# WiFiSensorLTC3559Spansion.net
KiCad netlist of a schematic drawn in EAGLE
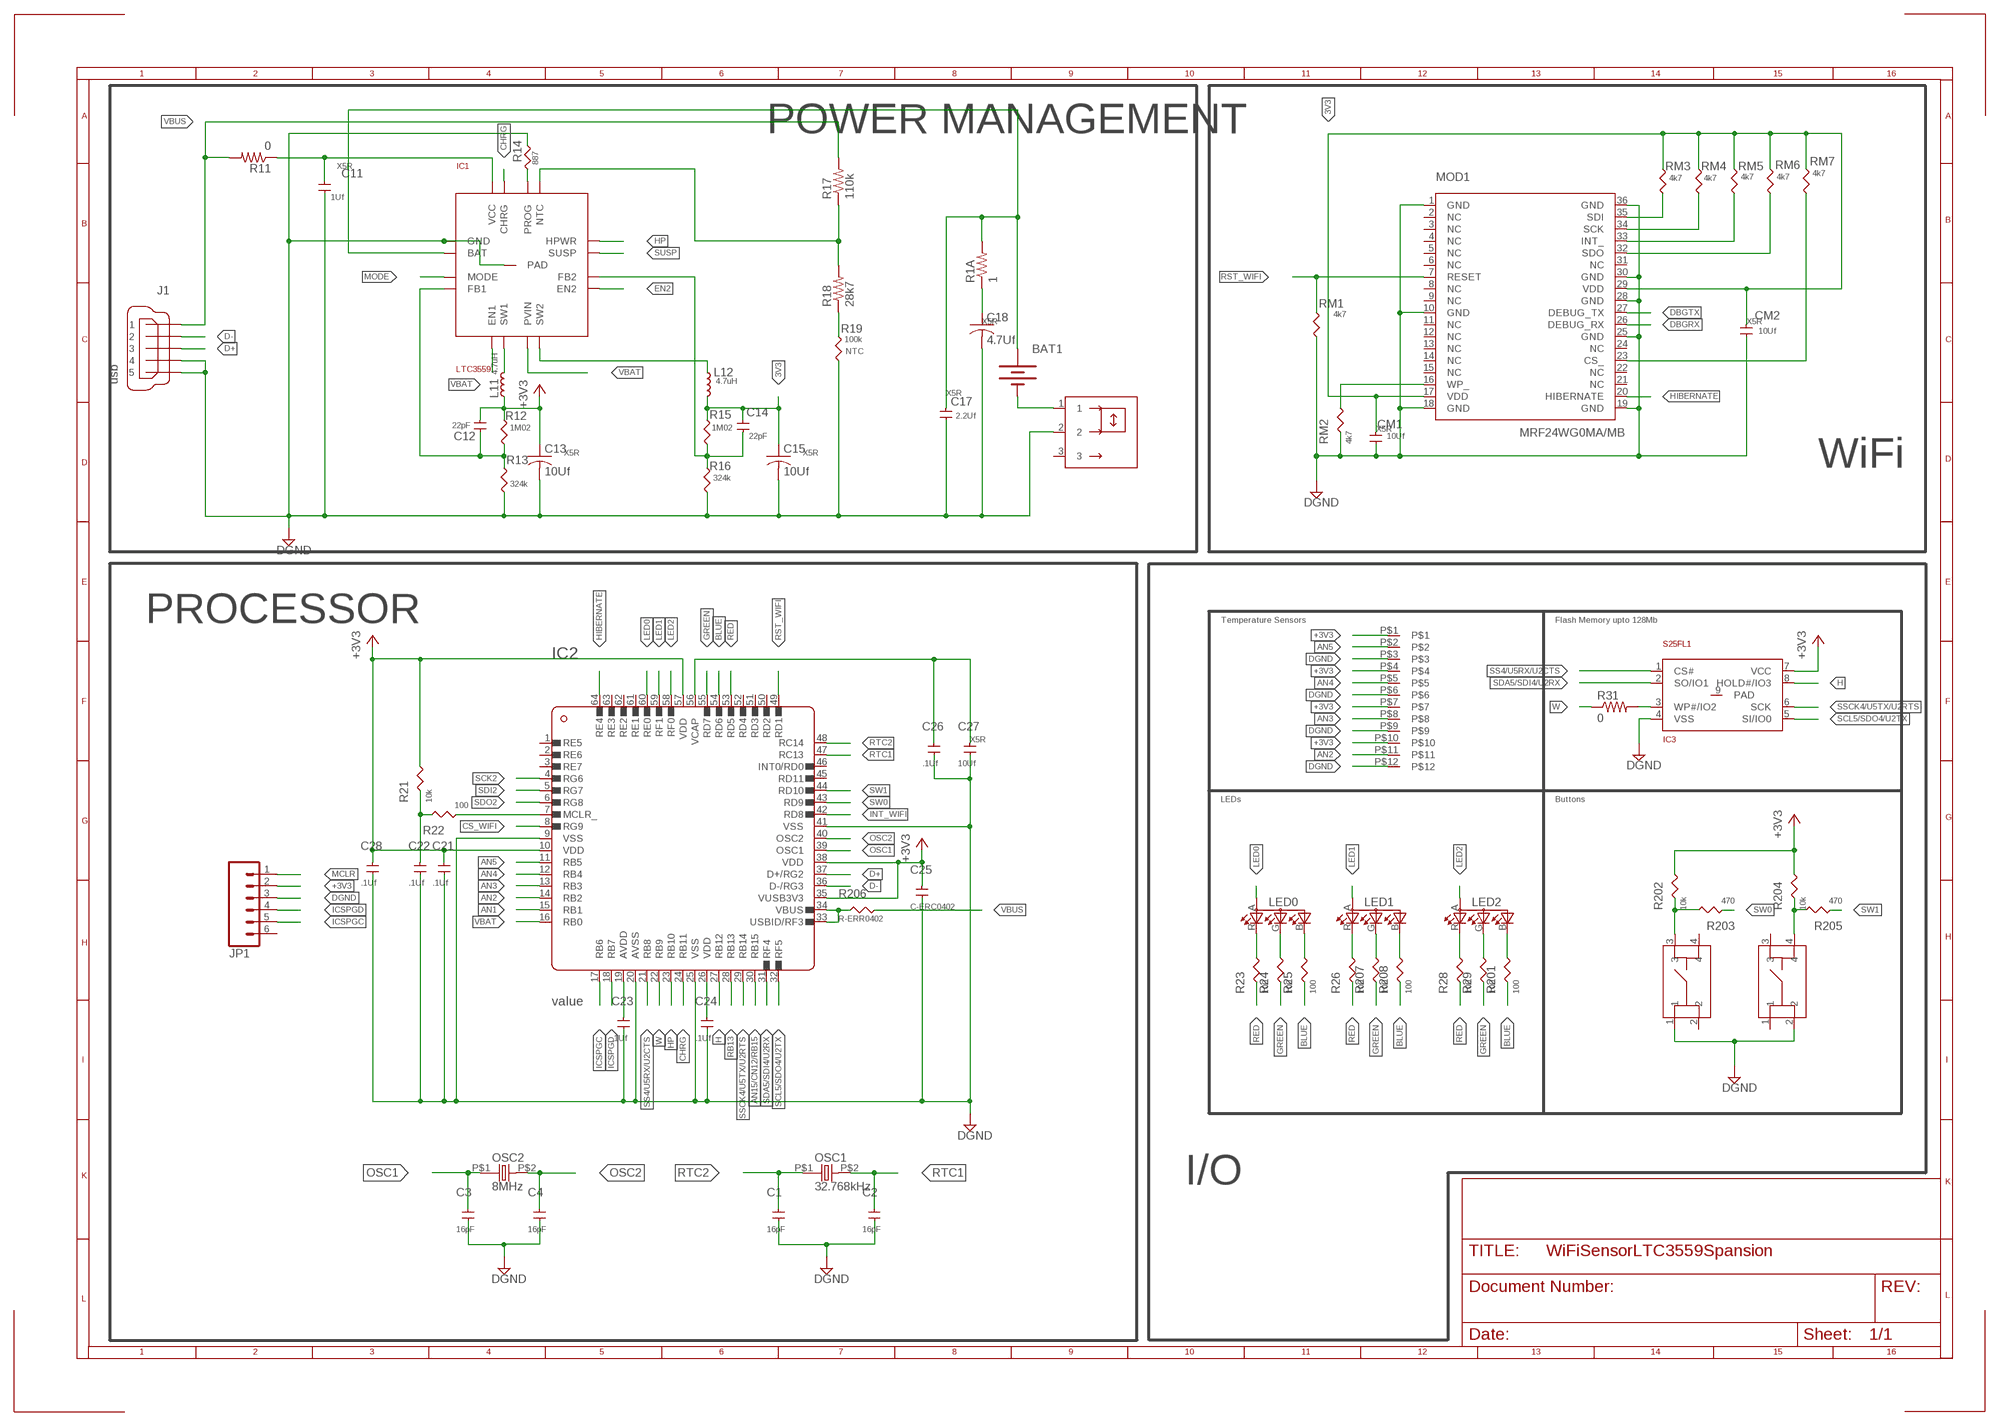
[diagram p0: schematic, sheet 1]

(export (version "E")
  (design (tool "Eeschema 10.0.6"))
  (components
    (comp (ref "BAT1")
      (value "BATTERY245PTH")
      (footprint "eagle-import:BATTCON_245MM_PTH")
      (libsource (lib "eagle-import") (part "BATTERY245PTH"))
    )
    (comp (ref "C1")
      (value "16pF")
      (footprint "eagle-import:C0402")
      (libsource (lib "eagle-import") (part "C-ERC0402"))
    )
    (comp (ref "C2")
      (value "16pF")
      (footprint "eagle-import:C0402")
      (libsource (lib "eagle-import") (part "C-ERC0402"))
    )
    (comp (ref "C3")
      (value "16pF")
      (footprint "eagle-import:C0402")
      (libsource (lib "eagle-import") (part "C-ERC0402"))
    )
    (comp (ref "C4")
      (value "16pF")
      (footprint "eagle-import:C0402")
      (libsource (lib "eagle-import") (part "C-ERC0402"))
    )
    (comp (ref "C11")
      (value "1Uf")
      (footprint "eagle-import:C0805")
      (fields (field (name "TEMPCHAR") "X5R"))
      (libsource (lib "eagle-import") (part "C-ER"))
    )
    (comp (ref "C12")
      (value "22pF")
      (footprint "eagle-import:C0402")
      (libsource (lib "eagle-import") (part "C-ERC0402"))
    )
    (comp (ref "C13")
      (value "10Uf")
      (footprint "eagle-import:C0805")
      (fields (field (name "TEMPCHAR") "X5R"))
      (libsource (lib "eagle-import") (part "C-USC0805"))
    )
    (comp (ref "C14")
      (value "22pF")
      (footprint "eagle-import:C0402")
      (libsource (lib "eagle-import") (part "C-ERC0402"))
    )
    (comp (ref "C15")
      (value "10Uf")
      (footprint "eagle-import:C0805")
      (fields (field (name "TEMPCHAR") "X5R"))
      (libsource (lib "eagle-import") (part "C-USC0805"))
    )
    (comp (ref "C17")
      (value "2.2Uf")
      (footprint "eagle-import:C0805")
      (fields (field (name "TEMPCHAR") "X5R"))
      (libsource (lib "eagle-import") (part "C-ER"))
    )
    (comp (ref "C18")
      (value "4.7Uf")
      (footprint "eagle-import:C0402")
      (fields (field (name "TEMPCHAR") "X5R"))
      (libsource (lib "eagle-import") (part "C-USC0402"))
    )
    (comp (ref "C21")
      (value ".1Uf")
      (footprint "eagle-import:C0402")
      (libsource (lib "eagle-import") (part "C-ERC0402"))
    )
    (comp (ref "C22")
      (value ".1Uf")
      (footprint "eagle-import:C0402")
      (libsource (lib "eagle-import") (part "C-ERC0402"))
    )
    (comp (ref "C23")
      (value ".1Uf")
      (footprint "eagle-import:C0402")
      (libsource (lib "eagle-import") (part "C-ERC0402"))
    )
    (comp (ref "C24")
      (value ".1Uf")
      (footprint "eagle-import:C0402")
      (libsource (lib "eagle-import") (part "C-ERC0402"))
    )
    (comp (ref "C25")
      (value "C-ERC0402")
      (footprint "eagle-import:C0402")
      (libsource (lib "eagle-import") (part "C-ERC0402"))
    )
    (comp (ref "C26")
      (value ".1Uf")
      (footprint "eagle-import:C0402")
      (libsource (lib "eagle-import") (part "C-ERC0402"))
    )
    (comp (ref "C27")
      (value "10Uf")
      (footprint "eagle-import:C0805")
      (fields (field (name "TEMPCHAR") "X5R"))
      (libsource (lib "eagle-import") (part "C-ER"))
    )
    (comp (ref "C28")
      (value ".1Uf")
      (footprint "eagle-import:C0402")
      (libsource (lib "eagle-import") (part "C-ERC0402"))
    )
    (comp (ref "CM1")
      (value "10Uf")
      (footprint "eagle-import:C0805")
      (fields (field (name "TEMPCHAR") "X5R"))
      (libsource (lib "eagle-import") (part "C-ER"))
    )
    (comp (ref "CM2")
      (value "10Uf")
      (footprint "eagle-import:C0805")
      (fields (field (name "TEMPCHAR") "X5R"))
      (libsource (lib "eagle-import") (part "C-ER"))
    )
    (comp (ref "IC1")
      (value "LTC3559")
      (footprint "eagle-import:QFN16")
      (libsource (lib "eagle-import") (part "LTC3559"))
    )
    (comp (ref "IC2")
      (value "PICMX32695F512H")
      (footprint "eagle-import:TQFP64")
      (libsource (lib "eagle-import") (part "PICMX32695F512H"))
    )
    (comp (ref "IC3")
      (value "S25FL1")
      (footprint "eagle-import:8WSON")
      (libsource (lib "eagle-import") (part "S25FL1"))
    )
    (comp (ref "J1")
      (value "usb")
      (footprint "eagle-import:UX60A-MB-5ST")
      (libsource (lib "eagle-import") (part "MINI-USB-UX60A-MB-5ST"))
    )
    (comp (ref "JP1")
      (value "M06LOCK")
      (footprint "eagle-import:1X06_LOCK")
      (libsource (lib "eagle-import") (part "M06LOCK"))
    )
    (comp (ref "L11")
      (value "4.7uH")
      (footprint "eagle-import:L3010")
      (libsource (lib "eagle-import") (part "L-ER"))
    )
    (comp (ref "L12")
      (value "4.7uH")
      (footprint "eagle-import:L3010")
      (libsource (lib "eagle-import") (part "L-ER"))
    )
    (comp (ref "LED0")
      (value "1X1RGB")
      (footprint "eagle-import:1X1")
      (libsource (lib "eagle-import") (part "1X1RGB"))
    )
    (comp (ref "LED1")
      (value "1X1RGB")
      (footprint "eagle-import:1X1")
      (libsource (lib "eagle-import") (part "1X1RGB"))
    )
    (comp (ref "LED2")
      (value "1X1RGB")
      (footprint "eagle-import:1X1")
      (libsource (lib "eagle-import") (part "1X1RGB"))
    )
    (comp (ref "MOD1")
      (value "MRF24WG0MA/MB")
      (footprint "eagle-import:MRF24")
      (libsource (lib "eagle-import") (part "MRF24WG0MA/MB"))
    )
    (comp (ref "OSC1")
      (value "32.768kHz")
      (footprint "eagle-import:ECX39")
      (fields (field (name "DIGIPART") "XC1658CT-ND"))
      (libsource (lib "eagle-import") (part "ECX32"))
    )
    (comp (ref "OSC2")
      (value "8MHz")
      (footprint "eagle-import:CX532")
      (fields (field (name "DIGIPART") "XC1658CT-ND"))
      (libsource (lib "eagle-import") (part "CX532"))
    )
    (comp (ref "R1A")
      (value "1")
      (footprint "eagle-import:R0402")
      (libsource (lib "eagle-import") (part "R-US_R0402"))
    )
    (comp (ref "R11")
      (value "0")
      (footprint "eagle-import:R1206")
      (libsource (lib "eagle-import") (part "R-US_R1206"))
    )
    (comp (ref "R12")
      (value "1M02")
      (footprint "eagle-import:R0402")
      (libsource (lib "eagle-import") (part "R-ERR0402"))
    )
    (comp (ref "R13")
      (value "324k")
      (footprint "eagle-import:R0402")
      (libsource (lib "eagle-import") (part "R-ERR0402"))
    )
    (comp (ref "R14")
      (value "887")
      (footprint "eagle-import:R0402")
      (libsource (lib "eagle-import") (part "R-ERR0402"))
    )
    (comp (ref "R15")
      (value "1M02")
      (footprint "eagle-import:R0402")
      (libsource (lib "eagle-import") (part "R-ERR0402"))
    )
    (comp (ref "R16")
      (value "324k")
      (footprint "eagle-import:R0402")
      (libsource (lib "eagle-import") (part "R-ERR0402"))
    )
    (comp (ref "R17")
      (value "110k")
      (footprint "eagle-import:M0805")
      (libsource (lib "eagle-import") (part "R-US_M0805"))
    )
    (comp (ref "R18")
      (value "28k7")
      (footprint "eagle-import:M1206")
      (libsource (lib "eagle-import") (part "R-US_M1206"))
    )
    (comp (ref "R19")
      (value "100k")
      (footprint "eagle-import:R0402")
      (fields (field (name "NTC") "NTC"))
      (libsource (lib "eagle-import") (part "R-ERR0402"))
    )
    (comp (ref "R21")
      (value "10k")
      (footprint "eagle-import:R0402")
      (libsource (lib "eagle-import") (part "R-ERR0402"))
    )
    (comp (ref "R22")
      (value "100")
      (footprint "eagle-import:R0402")
      (libsource (lib "eagle-import") (part "R-ERR0402"))
    )
    (comp (ref "R23")
      (value "100")
      (footprint "eagle-import:R0402")
      (libsource (lib "eagle-import") (part "R-ERR0402"))
    )
    (comp (ref "R24")
      (value "100")
      (footprint "eagle-import:R0402")
      (libsource (lib "eagle-import") (part "R-ERR0402"))
    )
    (comp (ref "R25")
      (value "100")
      (footprint "eagle-import:R0402")
      (libsource (lib "eagle-import") (part "R-ERR0402"))
    )
    (comp (ref "R26")
      (value "100")
      (footprint "eagle-import:R0402")
      (libsource (lib "eagle-import") (part "R-ERR0402"))
    )
    (comp (ref "R28")
      (value "100")
      (footprint "eagle-import:R0402")
      (libsource (lib "eagle-import") (part "R-ERR0402"))
    )
    (comp (ref "R29")
      (value "100")
      (footprint "eagle-import:R0402")
      (libsource (lib "eagle-import") (part "R-ERR0402"))
    )
    (comp (ref "R31")
      (value "0")
      (footprint "eagle-import:M0805")
      (libsource (lib "eagle-import") (part "R-US_M0805"))
    )
    (comp (ref "R201")
      (value "100")
      (footprint "eagle-import:R0402")
      (libsource (lib "eagle-import") (part "R-ERR0402"))
    )
    (comp (ref "R202")
      (value "10k")
      (footprint "eagle-import:R0402")
      (libsource (lib "eagle-import") (part "R-ERR0402"))
    )
    (comp (ref "R203")
      (value "470")
      (footprint "eagle-import:R0402")
      (libsource (lib "eagle-import") (part "R-ERR0402"))
    )
    (comp (ref "R204")
      (value "10k")
      (footprint "eagle-import:R0402")
      (libsource (lib "eagle-import") (part "R-ERR0402"))
    )
    (comp (ref "R205")
      (value "470")
      (footprint "eagle-import:R0402")
      (libsource (lib "eagle-import") (part "R-ERR0402"))
    )
    (comp (ref "R206")
      (value "R-ERR0402")
      (footprint "eagle-import:R0402")
      (libsource (lib "eagle-import") (part "R-ERR0402"))
    )
    (comp (ref "R207")
      (value "100")
      (footprint "eagle-import:R0402")
      (libsource (lib "eagle-import") (part "R-ERR0402"))
    )
    (comp (ref "R208")
      (value "100")
      (footprint "eagle-import:R0402")
      (libsource (lib "eagle-import") (part "R-ERR0402"))
    )
    (comp (ref "RM1")
      (value "4k7")
      (footprint "eagle-import:R0402")
      (libsource (lib "eagle-import") (part "R-ERR0402"))
    )
    (comp (ref "RM2")
      (value "4k7")
      (footprint "eagle-import:R0402")
      (libsource (lib "eagle-import") (part "R-ERR0402"))
    )
    (comp (ref "RM3")
      (value "4k7")
      (footprint "eagle-import:R0402")
      (libsource (lib "eagle-import") (part "R-ERR0402"))
    )
    (comp (ref "RM4")
      (value "4k7")
      (footprint "eagle-import:R0402")
      (libsource (lib "eagle-import") (part "R-ERR0402"))
    )
    (comp (ref "RM5")
      (value "4k7")
      (footprint "eagle-import:R0402")
      (libsource (lib "eagle-import") (part "R-ERR0402"))
    )
    (comp (ref "RM6")
      (value "4k7")
      (footprint "eagle-import:R0402")
      (libsource (lib "eagle-import") (part "R-ERR0402"))
    )
    (comp (ref "RM7")
      (value "4k7")
      (footprint "eagle-import:R0402")
      (libsource (lib "eagle-import") (part "R-ERR0402"))
    )
    (comp (ref "SENSORS")
      (value "12_127")
      (footprint "eagle-import:12-127")
      (libsource (lib "eagle-import") (part "12_127"))
    )
    (comp (ref "SW_ON")
      (value "C&K_JS")
      (footprint "eagle-import:SAQN")
      (libsource (lib "eagle-import") (part "C&K_JS"))
    )
    (comp (ref "U$2")
      (value "ADTS")
      (footprint "eagle-import:4X5")
      (libsource (lib "eagle-import") (part "ADTS"))
    )
    (comp (ref "U$3")
      (value "ADTS")
      (footprint "eagle-import:4X5")
      (libsource (lib "eagle-import") (part "ADTS"))
    )
  )
  (nets
    (net (code "1") (name "+3V3") (class "Default")
      (node (ref "C12") (pin "1") (pinfunction "P$1_1") (pintype "bidirectional"))
      (node (ref "C13") (pin "1") (pinfunction "1_1") (pintype "passive"))
      (node (ref "C21") (pin "2") (pinfunction "P$2_2") (pintype "bidirectional"))
      (node (ref "C23") (pin "2") (pinfunction "P$2_2") (pintype "bidirectional"))
      (node (ref "C24") (pin "2") (pinfunction "P$2_2") (pintype "bidirectional"))
      (node (ref "C25") (pin "2") (pinfunction "P$2_2") (pintype "bidirectional"))
      (node (ref "C28") (pin "2") (pinfunction "P$2_2") (pintype "bidirectional"))
      (node (ref "IC2") (pin "10") (pinfunction "VDD_10") (pintype "bidirectional"))
      (node (ref "IC2") (pin "19") (pinfunction "AVDD_19") (pintype "bidirectional"))
      (node (ref "IC2") (pin "26") (pinfunction "VDD_26") (pintype "bidirectional"))
      (node (ref "IC2") (pin "35") (pinfunction "VUSB3V3_35") (pintype "bidirectional"))
      (node (ref "IC2") (pin "38") (pinfunction "VDD_38") (pintype "bidirectional"))
      (node (ref "IC2") (pin "57") (pinfunction "VDD_57") (pintype "bidirectional"))
      (node (ref "IC3") (pin "7") (pinfunction "VCC_7") (pintype "bidirectional"))
      (node (ref "JP1") (pin "2") (pinfunction "2_2") (pintype "passive"))
      (node (ref "L11") (pin "P$1") (pinfunction "P$1_P$1") (pintype "bidirectional"))
      (node (ref "R12") (pin "2") (pinfunction "P$2_2") (pintype "bidirectional"))
      (node (ref "R202") (pin "2") (pinfunction "P$2_2") (pintype "bidirectional"))
      (node (ref "R204") (pin "2") (pinfunction "P$2_2") (pintype "bidirectional"))
      (node (ref "R21") (pin "2") (pinfunction "P$2_2") (pintype "bidirectional"))
      (node (ref "SENSORS") (pin "P$1") (pinfunction "P$1_P$1") (pintype "bidirectional"))
      (node (ref "SENSORS") (pin "P$10") (pinfunction "P$10_P$10") (pintype "bidirectional"))
      (node (ref "SENSORS") (pin "P$4") (pinfunction "P$4_P$4") (pintype "bidirectional"))
      (node (ref "SENSORS") (pin "P$7") (pinfunction "P$7_P$7") (pintype "bidirectional"))
    )
    (net (code "2") (name "3V3") (class "Default")
      (node (ref "C14") (pin "2") (pinfunction "P$2_2") (pintype "bidirectional"))
      (node (ref "C15") (pin "1") (pinfunction "1_1") (pintype "passive"))
      (node (ref "CM1") (pin "2") (pinfunction "P$2_2") (pintype "bidirectional"))
      (node (ref "CM2") (pin "2") (pinfunction "P$2_2") (pintype "bidirectional"))
      (node (ref "L12") (pin "P$2") (pinfunction "P$2_P$2") (pintype "bidirectional"))
      (node (ref "MOD1") (pin "17") (pinfunction "VDD_17") (pintype "bidirectional"))
      (node (ref "MOD1") (pin "29") (pinfunction "VDD_29") (pintype "bidirectional"))
      (node (ref "R15") (pin "2") (pinfunction "P$2_2") (pintype "bidirectional"))
      (node (ref "RM3") (pin "2") (pinfunction "P$2_2") (pintype "bidirectional"))
      (node (ref "RM4") (pin "2") (pinfunction "P$2_2") (pintype "bidirectional"))
      (node (ref "RM5") (pin "2") (pinfunction "P$2_2") (pintype "bidirectional"))
      (node (ref "RM6") (pin "2") (pinfunction "P$2_2") (pintype "bidirectional"))
      (node (ref "RM7") (pin "2") (pinfunction "P$2_2") (pintype "bidirectional"))
    )
    (net (code "3") (name "AN1") (class "Default")
      (node (ref "IC2") (pin "15") (pinfunction "RB1_15") (pintype "bidirectional"))
    )
    (net (code "4") (name "AN2") (class "Default")
      (node (ref "IC2") (pin "14") (pinfunction "RB2_14") (pintype "bidirectional"))
      (node (ref "SENSORS") (pin "P$11") (pinfunction "P$11_P$11") (pintype "bidirectional"))
    )
    (net (code "5") (name "AN3") (class "Default")
      (node (ref "IC2") (pin "13") (pinfunction "RB3_13") (pintype "bidirectional"))
      (node (ref "SENSORS") (pin "P$8") (pinfunction "P$8_P$8") (pintype "bidirectional"))
    )
    (net (code "6") (name "AN4") (class "Default")
      (node (ref "IC2") (pin "12") (pinfunction "RB4_12") (pintype "bidirectional"))
      (node (ref "SENSORS") (pin "P$5") (pinfunction "P$5_P$5") (pintype "bidirectional"))
    )
    (net (code "7") (name "AN5") (class "Default")
      (node (ref "IC2") (pin "11") (pinfunction "RB5_11") (pintype "bidirectional"))
      (node (ref "SENSORS") (pin "P$2") (pinfunction "P$2_P$2") (pintype "bidirectional"))
    )
    (net (code "8") (name "AN15{slash}CN12{slash}RB15") (class "Default")
      (node (ref "IC2") (pin "30") (pinfunction "RB15_30") (pintype "bidirectional"))
    )
    (net (code "9") (name "BLUE") (class "Default")
      (node (ref "IC2") (pin "54") (pinfunction "RD6_54") (pintype "bidirectional"))
      (node (ref "R201") (pin "1") (pinfunction "P$1_1") (pintype "bidirectional"))
      (node (ref "R208") (pin "1") (pinfunction "P$1_1") (pintype "bidirectional"))
      (node (ref "R25") (pin "1") (pinfunction "P$1_1") (pintype "bidirectional"))
    )
    (net (code "10") (name "CHRG") (class "Default")
      (node (ref "IC1") (pin "15") (pinfunction "CHRG_15") (pintype "bidirectional"))
      (node (ref "IC2") (pin "24") (pinfunction "RB11_24") (pintype "bidirectional"))
    )
    (net (code "11") (name "CS_WIFI") (class "Default")
      (node (ref "IC2") (pin "8") (pinfunction "RG9_8") (pintype "bidirectional"))
      (node (ref "MOD1") (pin "23") (pinfunction "CS__23") (pintype "bidirectional"))
      (node (ref "RM7") (pin "1") (pinfunction "P$1_1") (pintype "bidirectional"))
    )
    (net (code "12") (name "D+") (class "Default")
      (node (ref "IC2") (pin "37") (pinfunction "D+/RG2_37") (pintype "bidirectional"))
      (node (ref "J1") (pin "3") (pinfunction "3_3") (pintype "input"))
    )
    (net (code "13") (name "D-") (class "Default")
      (node (ref "IC2") (pin "36") (pinfunction "D-/RG3_36") (pintype "bidirectional"))
      (node (ref "J1") (pin "2") (pinfunction "2_2") (pintype "input"))
    )
    (net (code "14") (name "DBGRX") (class "Default")
      (node (ref "MOD1") (pin "26") (pinfunction "DEBUG_RX_26") (pintype "bidirectional"))
    )
    (net (code "15") (name "DBGTX") (class "Default")
      (node (ref "MOD1") (pin "27") (pinfunction "DEBUG_TX_27") (pintype "bidirectional"))
    )
    (net (code "16") (name "DGND") (class "Default")
      (node (ref "C1") (pin "1") (pinfunction "P$1_1") (pintype "bidirectional"))
      (node (ref "C11") (pin "1") (pinfunction "P$1_1") (pintype "bidirectional"))
      (node (ref "C13") (pin "2") (pinfunction "2_2") (pintype "passive"))
      (node (ref "C15") (pin "2") (pinfunction "2_2") (pintype "passive"))
      (node (ref "C17") (pin "1") (pinfunction "P$1_1") (pintype "bidirectional"))
      (node (ref "C18") (pin "2") (pinfunction "2_2") (pintype "passive"))
      (node (ref "C2") (pin "1") (pinfunction "P$1_1") (pintype "bidirectional"))
      (node (ref "C21") (pin "1") (pinfunction "P$1_1") (pintype "bidirectional"))
      (node (ref "C22") (pin "1") (pinfunction "P$1_1") (pintype "bidirectional"))
      (node (ref "C23") (pin "1") (pinfunction "P$1_1") (pintype "bidirectional"))
      (node (ref "C24") (pin "1") (pinfunction "P$1_1") (pintype "bidirectional"))
      (node (ref "C25") (pin "1") (pinfunction "P$1_1") (pintype "bidirectional"))
      (node (ref "C26") (pin "1") (pinfunction "P$1_1") (pintype "bidirectional"))
      (node (ref "C27") (pin "1") (pinfunction "P$1_1") (pintype "bidirectional"))
      (node (ref "C28") (pin "1") (pinfunction "P$1_1") (pintype "bidirectional"))
      (node (ref "C3") (pin "1") (pinfunction "P$1_1") (pintype "bidirectional"))
      (node (ref "C4") (pin "1") (pinfunction "P$1_1") (pintype "bidirectional"))
      (node (ref "CM1") (pin "1") (pinfunction "P$1_1") (pintype "bidirectional"))
      (node (ref "CM2") (pin "1") (pinfunction "P$1_1") (pintype "bidirectional"))
      (node (ref "IC1") (pin "1") (pinfunction "GND_1") (pintype "bidirectional"))
      (node (ref "IC1") (pin "P$17") (pinfunction "PAD_P$17") (pintype "bidirectional"))
      (node (ref "IC2") (pin "20") (pinfunction "AVSS_20") (pintype "bidirectional"))
      (node (ref "IC2") (pin "25") (pinfunction "VSS_25") (pintype "bidirectional"))
      (node (ref "IC2") (pin "41") (pinfunction "VSS_41") (pintype "bidirectional"))
      (node (ref "IC2") (pin "9") (pinfunction "VSS_9") (pintype "bidirectional"))
      (node (ref "IC3") (pin "4") (pinfunction "VSS_4") (pintype "bidirectional"))
      (node (ref "J1") (pin "4") (pinfunction "4_4") (pintype "input"))
      (node (ref "J1") (pin "5") (pinfunction "5_5") (pintype "input"))
      (node (ref "JP1") (pin "3") (pinfunction "3_3") (pintype "passive"))
      (node (ref "MOD1") (pin "1") (pinfunction "GND_1") (pintype "bidirectional"))
      (node (ref "MOD1") (pin "10") (pinfunction "GND_10") (pintype "bidirectional"))
      (node (ref "MOD1") (pin "18") (pinfunction "GND_18") (pintype "bidirectional"))
      (node (ref "MOD1") (pin "19") (pinfunction "GND_19") (pintype "bidirectional"))
      (node (ref "MOD1") (pin "25") (pinfunction "GND_25") (pintype "bidirectional"))
      (node (ref "MOD1") (pin "28") (pinfunction "GND_28") (pintype "bidirectional"))
      (node (ref "MOD1") (pin "30") (pinfunction "GND_30") (pintype "bidirectional"))
      (node (ref "MOD1") (pin "36") (pinfunction "GND_36") (pintype "bidirectional"))
      (node (ref "R13") (pin "1") (pinfunction "P$1_1") (pintype "bidirectional"))
      (node (ref "R14") (pin "1") (pinfunction "P$1_1") (pintype "bidirectional"))
      (node (ref "R16") (pin "1") (pinfunction "P$1_1") (pintype "bidirectional"))
      (node (ref "R19") (pin "1") (pinfunction "P$1_1") (pintype "bidirectional"))
      (node (ref "RM1") (pin "1") (pinfunction "P$1_1") (pintype "bidirectional"))
      (node (ref "RM2") (pin "1") (pinfunction "P$1_1") (pintype "bidirectional"))
      (node (ref "SENSORS") (pin "P$12") (pinfunction "P$12_P$12") (pintype "bidirectional"))
      (node (ref "SENSORS") (pin "P$3") (pinfunction "P$3_P$3") (pintype "bidirectional"))
      (node (ref "SENSORS") (pin "P$6") (pinfunction "P$6_P$6") (pintype "bidirectional"))
      (node (ref "SENSORS") (pin "P$9") (pinfunction "P$9_P$9") (pintype "bidirectional"))
      (node (ref "SW_ON") (pin "2") (pinfunction "2_2") (pintype "bidirectional"))
      (node (ref "U$2") (pin "2") (pinfunction "2_2") (pintype "bidirectional"))
      (node (ref "U$3") (pin "1") (pinfunction "1_1") (pintype "bidirectional"))
    )
    (net (code "17") (name "EN2") (class "Default")
      (node (ref "IC1") (pin "9") (pinfunction "EN2_9") (pintype "bidirectional"))
    )
    (net (code "18") (name "GREEN") (class "Default")
      (node (ref "IC2") (pin "55") (pinfunction "RD7_55") (pintype "bidirectional"))
      (node (ref "R207") (pin "1") (pinfunction "P$1_1") (pintype "bidirectional"))
      (node (ref "R24") (pin "1") (pinfunction "P$1_1") (pintype "bidirectional"))
      (node (ref "R29") (pin "1") (pinfunction "P$1_1") (pintype "bidirectional"))
    )
    (net (code "19") (name "H") (class "Default")
      (node (ref "IC2") (pin "27") (pinfunction "RB12_27") (pintype "bidirectional"))
      (node (ref "IC3") (pin "8") (pinfunction "HOLD#/IO3_8") (pintype "bidirectional"))
    )
    (net (code "20") (name "HIBERNATE") (class "Default")
      (node (ref "IC2") (pin "64") (pinfunction "RE4_64") (pintype "bidirectional"))
      (node (ref "MOD1") (pin "20") (pinfunction "HIBERNATE_20") (pintype "bidirectional"))
    )
    (net (code "21") (name "HP") (class "Default")
      (node (ref "IC1") (pin "12") (pinfunction "HPWR_12") (pintype "bidirectional"))
      (node (ref "IC2") (pin "23") (pinfunction "RB10_23") (pintype "bidirectional"))
    )
    (net (code "22") (name "ICSPGC") (class "Default")
      (node (ref "IC2") (pin "17") (pinfunction "RB6_17") (pintype "bidirectional"))
      (node (ref "JP1") (pin "5") (pinfunction "5_5") (pintype "passive"))
    )
    (net (code "23") (name "ICSPGD") (class "Default")
      (node (ref "IC2") (pin "18") (pinfunction "RB7_18") (pintype "bidirectional"))
      (node (ref "JP1") (pin "4") (pinfunction "4_4") (pintype "passive"))
    )
    (net (code "24") (name "INT_WIFI") (class "Default")
      (node (ref "IC2") (pin "42") (pinfunction "RD8_42") (pintype "bidirectional"))
      (node (ref "MOD1") (pin "33") (pinfunction "INT__33") (pintype "bidirectional"))
      (node (ref "RM5") (pin "1") (pinfunction "P$1_1") (pintype "bidirectional"))
    )
    (net (code "25") (name "LED0") (class "Default")
      (node (ref "IC2") (pin "60") (pinfunction "RE0_60") (pintype "bidirectional"))
      (node (ref "LED0") (pin "A") (pinfunction "A2_A") (pintype "passive"))
    )
    (net (code "26") (name "LED1") (class "Default")
      (node (ref "IC2") (pin "59") (pinfunction "RF1_59") (pintype "bidirectional"))
      (node (ref "LED1") (pin "A") (pinfunction "A2_A") (pintype "passive"))
    )
    (net (code "27") (name "LED2") (class "Default")
      (node (ref "IC2") (pin "58") (pinfunction "RF0_58") (pintype "bidirectional"))
      (node (ref "LED2") (pin "A") (pinfunction "A2_A") (pintype "passive"))
    )
    (net (code "28") (name "MCLR") (class "Default")
      (node (ref "C22") (pin "2") (pinfunction "P$2_2") (pintype "bidirectional"))
      (node (ref "JP1") (pin "1") (pinfunction "1_1") (pintype "passive"))
      (node (ref "R21") (pin "1") (pinfunction "P$1_1") (pintype "bidirectional"))
      (node (ref "R22") (pin "2") (pinfunction "P$2_2") (pintype "bidirectional"))
    )
    (net (code "29") (name "MODE") (class "Default")
      (node (ref "IC1") (pin "3") (pinfunction "MODE_3") (pintype "bidirectional"))
    )
    (net (code "30") (name "Net-(BAT1--)") (class "Default")
      (node (ref "BAT1") (pin "2") (pinfunction "-_2") (pintype "power_in"))
      (node (ref "SW_ON") (pin "1") (pinfunction "1_1") (pintype "bidirectional"))
    )
    (net (code "31") (name "Net-(C11-P$2)") (class "Default")
      (node (ref "C11") (pin "2") (pinfunction "P$2_2") (pintype "bidirectional"))
      (node (ref "IC1") (pin "16") (pinfunction "VCC_16") (pintype "bidirectional"))
      (node (ref "R11") (pin "1") (pinfunction "1_1") (pintype "passive"))
    )
    (net (code "32") (name "Net-(C12-P$2)") (class "Default")
      (node (ref "C12") (pin "2") (pinfunction "P$2_2") (pintype "bidirectional"))
      (node (ref "IC1") (pin "4") (pinfunction "FB1_4") (pintype "bidirectional"))
      (node (ref "R12") (pin "1") (pinfunction "P$1_1") (pintype "bidirectional"))
      (node (ref "R13") (pin "2") (pinfunction "P$2_2") (pintype "bidirectional"))
    )
    (net (code "33") (name "Net-(C14-P$1)") (class "Default")
      (node (ref "C14") (pin "1") (pinfunction "P$1_1") (pintype "bidirectional"))
      (node (ref "IC1") (pin "10") (pinfunction "FB2_10") (pintype "bidirectional"))
      (node (ref "R15") (pin "1") (pinfunction "P$1_1") (pintype "bidirectional"))
      (node (ref "R16") (pin "2") (pinfunction "P$2_2") (pintype "bidirectional"))
    )
    (net (code "34") (name "Net-(C18-Pad1)") (class "Default")
      (node (ref "C18") (pin "1") (pinfunction "1_1") (pintype "passive"))
      (node (ref "R1A") (pin "1") (pinfunction "1_1") (pintype "passive"))
    )
    (net (code "35") (name "Net-(C26-P$2)") (class "Default")
      (node (ref "C26") (pin "2") (pinfunction "P$2_2") (pintype "bidirectional"))
      (node (ref "C27") (pin "2") (pinfunction "P$2_2") (pintype "bidirectional"))
      (node (ref "IC2") (pin "56") (pinfunction "VCAP_56") (pintype "bidirectional"))
    )
    (net (code "36") (name "Net-(IC1-NTC)") (class "Default")
      (node (ref "IC1") (pin "13") (pinfunction "NTC_13") (pintype "bidirectional"))
      (node (ref "R17") (pin "1") (pinfunction "1_1") (pintype "passive"))
      (node (ref "R18") (pin "2") (pinfunction "2_2") (pintype "passive"))
    )
    (net (code "37") (name "Net-(IC1-PROG)") (class "Default")
      (node (ref "IC1") (pin "14") (pinfunction "PROG_14") (pintype "bidirectional"))
      (node (ref "R14") (pin "2") (pinfunction "P$2_2") (pintype "bidirectional"))
    )
    (net (code "38") (name "Net-(IC1-SW1)") (class "Default")
      (node (ref "IC1") (pin "6") (pinfunction "SW1_6") (pintype "bidirectional"))
      (node (ref "L11") (pin "P$2") (pinfunction "P$2_P$2") (pintype "bidirectional"))
    )
    (net (code "39") (name "Net-(IC1-SW2)") (class "Default")
      (node (ref "IC1") (pin "8") (pinfunction "SW2_8") (pintype "bidirectional"))
      (node (ref "L12") (pin "P$1") (pinfunction "P$1_P$1") (pintype "bidirectional"))
    )
    (net (code "40") (name "Net-(IC2-MCLR_)") (class "Default")
      (node (ref "IC2") (pin "7") (pinfunction "MCLR__7") (pintype "bidirectional"))
      (node (ref "R22") (pin "1") (pinfunction "P$1_1") (pintype "bidirectional"))
    )
    (net (code "41") (name "Net-(IC2-USBID{slash}RF3)") (class "Default")
      (node (ref "IC2") (pin "33") (pinfunction "USBID/RF3_33") (pintype "bidirectional"))
      (node (ref "IC2") (pin "34") (pinfunction "VBUS_34") (pintype "bidirectional"))
      (node (ref "R206") (pin "1") (pinfunction "P$1_1") (pintype "bidirectional"))
    )
    (net (code "42") (name "Net-(IC3-WP#{slash}IO2)") (class "Default")
      (node (ref "IC3") (pin "3") (pinfunction "WP#/IO2_3") (pintype "bidirectional"))
      (node (ref "R31") (pin "2") (pinfunction "2_2") (pintype "passive"))
    )
    (net (code "43") (name "Net-(LED0-CBLUE)") (class "Default")
      (node (ref "LED0") (pin "G") (pinfunction "CBLUE_G") (pintype "passive"))
      (node (ref "R24") (pin "2") (pinfunction "P$2_2") (pintype "bidirectional"))
    )
    (net (code "44") (name "Net-(LED0-CGREEN)") (class "Default")
      (node (ref "LED0") (pin "B") (pinfunction "CGREEN_B") (pintype "passive"))
      (node (ref "R25") (pin "2") (pinfunction "P$2_2") (pintype "bidirectional"))
    )
    (net (code "45") (name "Net-(LED0-CRED)") (class "Default")
      (node (ref "LED0") (pin "R") (pinfunction "CRED_R") (pintype "passive"))
      (node (ref "R23") (pin "2") (pinfunction "P$2_2") (pintype "bidirectional"))
    )
    (net (code "46") (name "Net-(LED1-CBLUE)") (class "Default")
      (node (ref "LED1") (pin "G") (pinfunction "CBLUE_G") (pintype "passive"))
      (node (ref "R207") (pin "2") (pinfunction "P$2_2") (pintype "bidirectional"))
    )
    (net (code "47") (name "Net-(LED1-CGREEN)") (class "Default")
      (node (ref "LED1") (pin "B") (pinfunction "CGREEN_B") (pintype "passive"))
      (node (ref "R208") (pin "2") (pinfunction "P$2_2") (pintype "bidirectional"))
    )
    (net (code "48") (name "Net-(LED1-CRED)") (class "Default")
      (node (ref "LED1") (pin "R") (pinfunction "CRED_R") (pintype "passive"))
      (node (ref "R26") (pin "2") (pinfunction "P$2_2") (pintype "bidirectional"))
    )
    (net (code "49") (name "Net-(LED2-CBLUE)") (class "Default")
      (node (ref "LED2") (pin "G") (pinfunction "CBLUE_G") (pintype "passive"))
      (node (ref "R29") (pin "2") (pinfunction "P$2_2") (pintype "bidirectional"))
    )
    (net (code "50") (name "Net-(LED2-CGREEN)") (class "Default")
      (node (ref "LED2") (pin "B") (pinfunction "CGREEN_B") (pintype "passive"))
      (node (ref "R201") (pin "2") (pinfunction "P$2_2") (pintype "bidirectional"))
    )
    (net (code "51") (name "Net-(LED2-CRED)") (class "Default")
      (node (ref "LED2") (pin "R") (pinfunction "CRED_R") (pintype "passive"))
      (node (ref "R28") (pin "2") (pinfunction "P$2_2") (pintype "bidirectional"))
    )
    (net (code "52") (name "Net-(MOD1-WP_)") (class "Default")
      (node (ref "MOD1") (pin "16") (pinfunction "WP__16") (pintype "bidirectional"))
      (node (ref "RM2") (pin "2") (pinfunction "P$2_2") (pintype "bidirectional"))
    )
    (net (code "53") (name "Net-(R19-P$2)") (class "Default")
      (node (ref "R18") (pin "1") (pinfunction "1_1") (pintype "passive"))
      (node (ref "R19") (pin "2") (pinfunction "P$2_2") (pintype "bidirectional"))
    )
    (net (code "54") (name "Net-(R202-P$1)") (class "Default")
      (node (ref "R202") (pin "1") (pinfunction "P$1_1") (pintype "bidirectional"))
      (node (ref "R203") (pin "2") (pinfunction "P$2_2") (pintype "bidirectional"))
      (node (ref "U$3") (pin "3") (pinfunction "3_3") (pintype "bidirectional"))
    )
    (net (code "55") (name "Net-(R204-P$1)") (class "Default")
      (node (ref "R204") (pin "1") (pinfunction "P$1_1") (pintype "bidirectional"))
      (node (ref "R205") (pin "2") (pinfunction "P$2_2") (pintype "bidirectional"))
      (node (ref "U$2") (pin "4") (pinfunction "4_4") (pintype "bidirectional"))
    )
    (net (code "56") (name "OSC1") (class "Default")
      (node (ref "C3") (pin "2") (pinfunction "P$2_2") (pintype "bidirectional"))
      (node (ref "IC2") (pin "39") (pinfunction "OSC1_39") (pintype "bidirectional"))
      (node (ref "OSC2") (pin "P$1") (pinfunction "1_P$1") (pintype "passive"))
    )
    (net (code "57") (name "OSC2") (class "Default")
      (node (ref "C4") (pin "2") (pinfunction "P$2_2") (pintype "bidirectional"))
      (node (ref "IC2") (pin "40") (pinfunction "OSC2_40") (pintype "bidirectional"))
      (node (ref "OSC2") (pin "P$2") (pinfunction "2_P$2") (pintype "passive"))
    )
    (net (code "58") (name "RB13") (class "Default")
      (node (ref "IC2") (pin "28") (pinfunction "RB13_28") (pintype "bidirectional"))
    )
    (net (code "59") (name "RED") (class "Default")
      (node (ref "IC2") (pin "53") (pinfunction "RD5_53") (pintype "bidirectional"))
      (node (ref "R23") (pin "1") (pinfunction "P$1_1") (pintype "bidirectional"))
      (node (ref "R26") (pin "1") (pinfunction "P$1_1") (pintype "bidirectional"))
      (node (ref "R28") (pin "1") (pinfunction "P$1_1") (pintype "bidirectional"))
    )
    (net (code "60") (name "RST_WIFI") (class "Default")
      (node (ref "IC2") (pin "49") (pinfunction "RD1_49") (pintype "bidirectional"))
      (node (ref "MOD1") (pin "7") (pinfunction "RESET_7") (pintype "bidirectional"))
      (node (ref "RM1") (pin "2") (pinfunction "P$2_2") (pintype "bidirectional"))
    )
    (net (code "61") (name "RTC1") (class "Default")
      (node (ref "C2") (pin "2") (pinfunction "P$2_2") (pintype "bidirectional"))
      (node (ref "IC2") (pin "47") (pinfunction "RC13_47") (pintype "bidirectional"))
      (node (ref "OSC1") (pin "P$2") (pinfunction "2_P$2") (pintype "passive"))
    )
    (net (code "62") (name "RTC2") (class "Default")
      (node (ref "C1") (pin "2") (pinfunction "P$2_2") (pintype "bidirectional"))
      (node (ref "IC2") (pin "48") (pinfunction "RC14_48") (pintype "bidirectional"))
      (node (ref "OSC1") (pin "P$1") (pinfunction "1_P$1") (pintype "passive"))
    )
    (net (code "63") (name "SCK2") (class "Default")
      (node (ref "IC2") (pin "4") (pinfunction "RG6_4") (pintype "bidirectional"))
      (node (ref "MOD1") (pin "34") (pinfunction "SCK_34") (pintype "bidirectional"))
      (node (ref "RM4") (pin "1") (pinfunction "P$1_1") (pintype "bidirectional"))
    )
    (net (code "64") (name "SCL5{slash}SDO4{slash}U2TX") (class "Default")
      (node (ref "IC2") (pin "32") (pinfunction "RF5_32") (pintype "bidirectional"))
      (node (ref "IC3") (pin "5") (pinfunction "SI/IO0_5") (pintype "bidirectional"))
    )
    (net (code "65") (name "SDA5{slash}SDI4{slash}U2RX") (class "Default")
      (node (ref "IC2") (pin "31") (pinfunction "RF4_31") (pintype "bidirectional"))
      (node (ref "IC3") (pin "2") (pinfunction "SO/IO1_2") (pintype "bidirectional"))
    )
    (net (code "66") (name "SDI2") (class "Default")
      (node (ref "IC2") (pin "5") (pinfunction "RG7_5") (pintype "bidirectional"))
      (node (ref "MOD1") (pin "32") (pinfunction "SDO_32") (pintype "bidirectional"))
      (node (ref "RM6") (pin "1") (pinfunction "P$1_1") (pintype "bidirectional"))
    )
    (net (code "67") (name "SDO2") (class "Default")
      (node (ref "IC2") (pin "6") (pinfunction "RG8_6") (pintype "bidirectional"))
      (node (ref "MOD1") (pin "35") (pinfunction "SDI_35") (pintype "bidirectional"))
      (node (ref "RM3") (pin "1") (pinfunction "P$1_1") (pintype "bidirectional"))
    )
    (net (code "68") (name "SS4{slash}U5RX{slash}U2CTS") (class "Default")
      (node (ref "IC2") (pin "21") (pinfunction "RB8_21") (pintype "bidirectional"))
      (node (ref "IC3") (pin "1") (pinfunction "CS#_1") (pintype "bidirectional"))
    )
    (net (code "69") (name "SSCK4{slash}U5TX{slash}U2RTS") (class "Default")
      (node (ref "IC2") (pin "29") (pinfunction "RB14_29") (pintype "bidirectional"))
      (node (ref "IC3") (pin "6") (pinfunction "SCK_6") (pintype "bidirectional"))
    )
    (net (code "70") (name "SUSP") (class "Default")
      (node (ref "IC1") (pin "11") (pinfunction "SUSP_11") (pintype "bidirectional"))
    )
    (net (code "71") (name "SW0") (class "Default")
      (node (ref "IC2") (pin "43") (pinfunction "RD9_43") (pintype "bidirectional"))
      (node (ref "R203") (pin "1") (pinfunction "P$1_1") (pintype "bidirectional"))
    )
    (net (code "72") (name "SW1") (class "Default")
      (node (ref "IC2") (pin "44") (pinfunction "RD10_44") (pintype "bidirectional"))
      (node (ref "R205") (pin "1") (pinfunction "P$1_1") (pintype "bidirectional"))
    )
    (net (code "73") (name "VBAT") (class "Default")
      (node (ref "BAT1") (pin "3") (pinfunction "+_3") (pintype "power_in"))
      (node (ref "C17") (pin "2") (pinfunction "P$2_2") (pintype "bidirectional"))
      (node (ref "IC1") (pin "2") (pinfunction "BAT_2") (pintype "bidirectional"))
      (node (ref "IC1") (pin "5") (pinfunction "EN1_5") (pintype "bidirectional"))
      (node (ref "IC1") (pin "7") (pinfunction "PVIN_7") (pintype "bidirectional"))
      (node (ref "IC2") (pin "16") (pinfunction "RB0_16") (pintype "bidirectional"))
      (node (ref "R1A") (pin "2") (pinfunction "2_2") (pintype "passive"))
    )
    (net (code "74") (name "VBUS") (class "Default")
      (node (ref "J1") (pin "1") (pinfunction "1_1") (pintype "input"))
      (node (ref "R11") (pin "2") (pinfunction "2_2") (pintype "passive"))
      (node (ref "R17") (pin "2") (pinfunction "2_2") (pintype "passive"))
      (node (ref "R206") (pin "2") (pinfunction "P$2_2") (pintype "bidirectional"))
    )
    (net (code "75") (name "W") (class "Default")
      (node (ref "IC2") (pin "22") (pinfunction "RB9_22") (pintype "bidirectional"))
      (node (ref "R31") (pin "1") (pinfunction "1_1") (pintype "passive"))
    )
    (net (code "76") (name "unconnected-(IC2-INT0{slash}RD0-Pad46)") (class "Default")
      (node (ref "IC2") (pin "46") (pinfunction "INT0/RD0_46") (pintype "bidirectional"))
    )
    (net (code "77") (name "unconnected-(IC2-RD2-Pad50)") (class "Default")
      (node (ref "IC2") (pin "50") (pinfunction "RD2_50") (pintype "bidirectional"))
    )
    (net (code "78") (name "unconnected-(IC2-RD3-Pad51)") (class "Default")
      (node (ref "IC2") (pin "51") (pinfunction "RD3_51") (pintype "bidirectional"))
    )
    (net (code "79") (name "unconnected-(IC2-RD4-Pad52)") (class "Default")
      (node (ref "IC2") (pin "52") (pinfunction "RD4_52") (pintype "bidirectional"))
    )
    (net (code "80") (name "unconnected-(IC2-RD11-Pad45)") (class "Default")
      (node (ref "IC2") (pin "45") (pinfunction "RD11_45") (pintype "bidirectional"))
    )
    (net (code "81") (name "unconnected-(IC2-RE1-Pad61)") (class "Default")
      (node (ref "IC2") (pin "61") (pinfunction "RE1_61") (pintype "bidirectional"))
    )
    (net (code "82") (name "unconnected-(IC2-RE2-Pad62)") (class "Default")
      (node (ref "IC2") (pin "62") (pinfunction "RE2_62") (pintype "bidirectional"))
    )
    (net (code "83") (name "unconnected-(IC2-RE3-Pad63)") (class "Default")
      (node (ref "IC2") (pin "63") (pinfunction "RE3_63") (pintype "bidirectional"))
    )
    (net (code "84") (name "unconnected-(IC2-RE5-Pad1)") (class "Default")
      (node (ref "IC2") (pin "1") (pinfunction "RE5_1") (pintype "bidirectional"))
    )
    (net (code "85") (name "unconnected-(IC2-RE6-Pad2)") (class "Default")
      (node (ref "IC2") (pin "2") (pinfunction "RE6_2") (pintype "bidirectional"))
    )
    (net (code "86") (name "unconnected-(IC2-RE7-Pad3)") (class "Default")
      (node (ref "IC2") (pin "3") (pinfunction "RE7_3") (pintype "bidirectional"))
    )
    (net (code "87") (name "unconnected-(IC3-PAD-Pad9)") (class "Default")
      (node (ref "IC3") (pin "9") (pinfunction "PAD_9") (pintype "bidirectional"))
    )
    (net (code "88") (name "unconnected-(JP1-Pad6)") (class "Default")
      (node (ref "JP1") (pin "6") (pinfunction "6_6") (pintype "passive"))
    )
    (net (code "89") (name "unconnected-(MOD1-NC-Pad2)") (class "Default")
      (node (ref "MOD1") (pin "2") (pinfunction "NC_2") (pintype "bidirectional"))
    )
    (net (code "90") (name "unconnected-(MOD1-NC-Pad3)") (class "Default")
      (node (ref "MOD1") (pin "3") (pinfunction "NC_3") (pintype "bidirectional"))
    )
    (net (code "91") (name "unconnected-(MOD1-NC-Pad4)") (class "Default")
      (node (ref "MOD1") (pin "4") (pinfunction "NC_4") (pintype "bidirectional"))
    )
    (net (code "92") (name "unconnected-(MOD1-NC-Pad5)") (class "Default")
      (node (ref "MOD1") (pin "5") (pinfunction "NC_5") (pintype "bidirectional"))
    )
    (net (code "93") (name "unconnected-(MOD1-NC-Pad6)") (class "Default")
      (node (ref "MOD1") (pin "6") (pinfunction "NC_6") (pintype "bidirectional"))
    )
    (net (code "94") (name "unconnected-(MOD1-NC-Pad8)") (class "Default")
      (node (ref "MOD1") (pin "8") (pinfunction "NC_8") (pintype "bidirectional"))
    )
    (net (code "95") (name "unconnected-(MOD1-NC-Pad9)") (class "Default")
      (node (ref "MOD1") (pin "9") (pinfunction "NC_9") (pintype "bidirectional"))
    )
    (net (code "96") (name "unconnected-(MOD1-NC-Pad11)") (class "Default")
      (node (ref "MOD1") (pin "11") (pinfunction "NC_11") (pintype "bidirectional"))
    )
    (net (code "97") (name "unconnected-(MOD1-NC-Pad12)") (class "Default")
      (node (ref "MOD1") (pin "12") (pinfunction "NC_12") (pintype "bidirectional"))
    )
    (net (code "98") (name "unconnected-(MOD1-NC-Pad13)") (class "Default")
      (node (ref "MOD1") (pin "13") (pinfunction "NC_13") (pintype "bidirectional"))
    )
    (net (code "99") (name "unconnected-(MOD1-NC-Pad14)") (class "Default")
      (node (ref "MOD1") (pin "14") (pinfunction "NC_14") (pintype "bidirectional"))
    )
    (net (code "100") (name "unconnected-(MOD1-NC-Pad15)") (class "Default")
      (node (ref "MOD1") (pin "15") (pinfunction "NC_15") (pintype "bidirectional"))
    )
    (net (code "101") (name "unconnected-(MOD1-NC-Pad21)") (class "Default")
      (node (ref "MOD1") (pin "21") (pinfunction "NC_21") (pintype "bidirectional"))
    )
    (net (code "102") (name "unconnected-(MOD1-NC-Pad22)") (class "Default")
      (node (ref "MOD1") (pin "22") (pinfunction "NC_22") (pintype "bidirectional"))
    )
    (net (code "103") (name "unconnected-(MOD1-NC-Pad24)") (class "Default")
      (node (ref "MOD1") (pin "24") (pinfunction "NC_24") (pintype "bidirectional"))
    )
    (net (code "104") (name "unconnected-(MOD1-NC-Pad31)") (class "Default")
      (node (ref "MOD1") (pin "31") (pinfunction "NC_31") (pintype "bidirectional"))
    )
    (net (code "105") (name "unconnected-(SW_ON-Pad3)") (class "Default")
      (node (ref "SW_ON") (pin "3") (pinfunction "3_3") (pintype "bidirectional"))
    )
    (net (code "106") (name "unconnected-(U$2-Pad1)") (class "Default")
      (node (ref "U$2") (pin "1") (pinfunction "1_1") (pintype "bidirectional"))
    )
    (net (code "107") (name "unconnected-(U$2-Pad3)") (class "Default")
      (node (ref "U$2") (pin "3") (pinfunction "3_3") (pintype "bidirectional"))
    )
    (net (code "108") (name "unconnected-(U$3-Pad2)") (class "Default")
      (node (ref "U$3") (pin "2") (pinfunction "2_2") (pintype "bidirectional"))
    )
    (net (code "109") (name "unconnected-(U$3-Pad4)") (class "Default")
      (node (ref "U$3") (pin "4") (pinfunction "4_4") (pintype "bidirectional"))
    )
  )
)
